# SA_Sch.net
KiCad netlist of a schematic drawn in Altium Designer
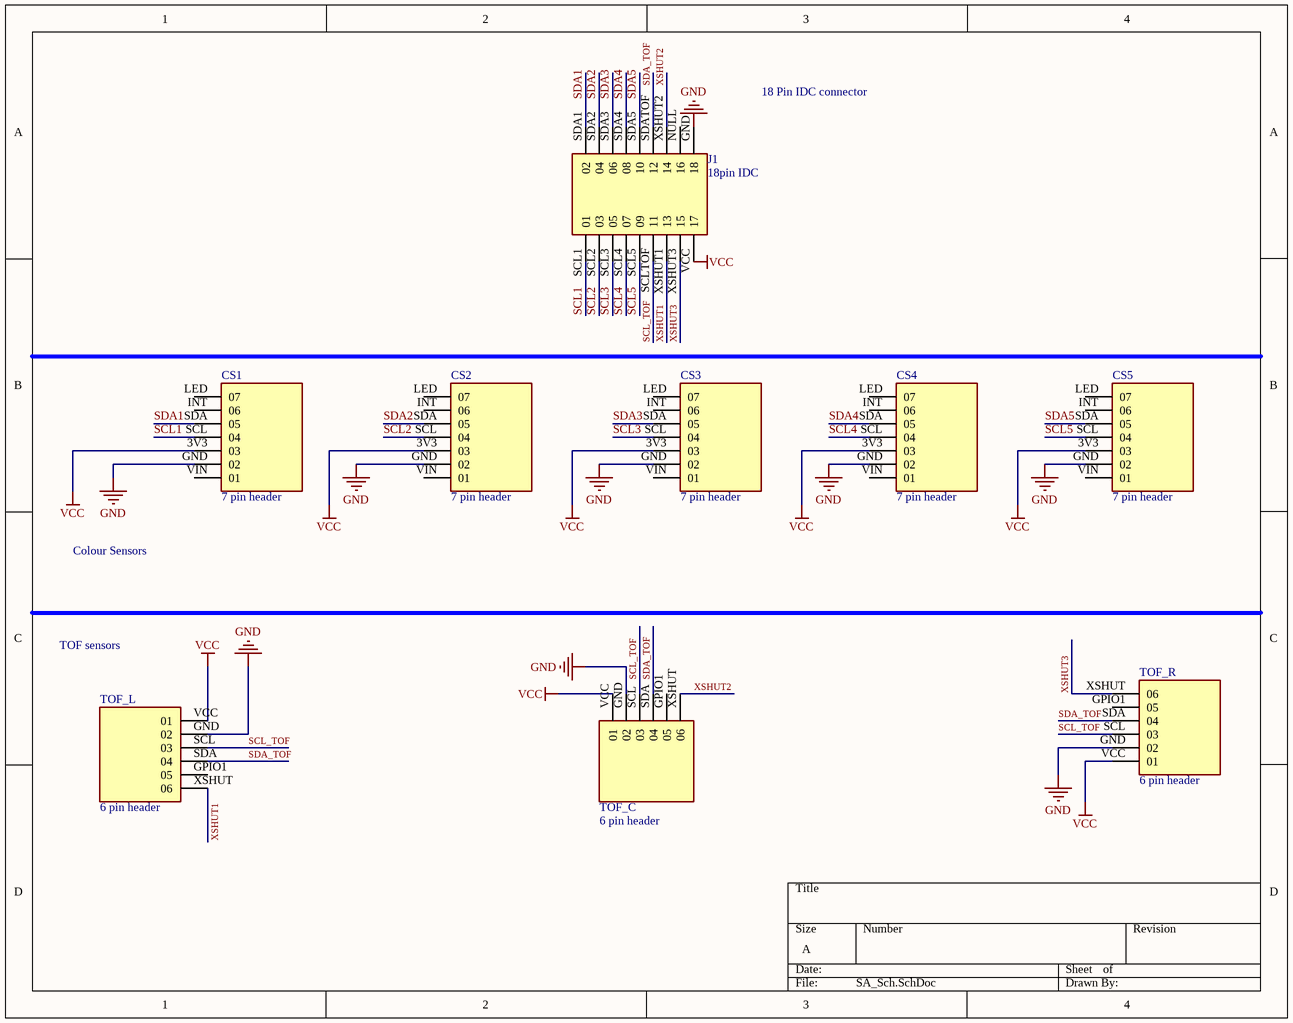
[diagram p0: SA_Sch.SchDoc]

(export (version "E")
  (design (tool "Eeschema 10.0.6"))
  (components
    (comp (ref "CS1")
      (value "7 pin header")
      (footprint "7 pin header holes")
      (description "14 Position Header Connector Male Pin Gold")
      (fields (field (name "MF") "Samtec") (field (name "MP") "TS-114-G-AA"))
      (libsource (lib "SA_SchLib") (part "7 pin header"))
    )
    (comp (ref "CS2")
      (value "7 pin header")
      (footprint "7 pin header holes")
      (description "14 Position Header Connector Male Pin Gold")
      (fields (field (name "MF") "Samtec") (field (name "MP") "TS-114-G-AA"))
      (libsource (lib "SA_SchLib") (part "7 pin header"))
    )
    (comp (ref "CS3")
      (value "7 pin header")
      (footprint "7 pin header holes")
      (description "14 Position Header Connector Male Pin Gold")
      (fields (field (name "MF") "Samtec") (field (name "MP") "TS-114-G-AA"))
      (libsource (lib "SA_SchLib") (part "7 pin header"))
    )
    (comp (ref "CS4")
      (value "7 pin header")
      (footprint "7 pin header holes")
      (description "14 Position Header Connector Male Pin Gold")
      (fields (field (name "MF") "Samtec") (field (name "MP") "TS-114-G-AA"))
      (libsource (lib "SA_SchLib") (part "7 pin header"))
    )
    (comp (ref "CS5")
      (value "7 pin header")
      (footprint "7 pin header holes")
      (description "14 Position Header Connector Male Pin Gold")
      (fields (field (name "MF") "Samtec") (field (name "MP") "TS-114-G-AA"))
      (libsource (lib "SA_SchLib") (part "7 pin header"))
    )
    (comp (ref "J1")
      (value "18pin IDC")
      (footprint "IDC 18 pin")
      (description "Slim Body Double-Row IDC Male Assemblies, 0.100 Pitch")
      (fields (field (name "MF") "SAMTEC") (field (name "MP") "IDMD-10-S-07.00-G"))
      (libsource (lib "SA_SchLib") (part "18pin IDC"))
    )
    (comp (ref "TOF_C")
      (value "6 pin header")
      (footprint "6 pin header")
      (description "6 Position Header Connector Male Pin Gold")
      (fields (field (name "MF") "Samtec") (field (name "MP") "TS-114-G-AA"))
      (libsource (lib "") (part "6 pin header_2"))
    )
    (comp (ref "TOF_L")
      (value "6 pin header")
      (footprint "6 pin header")
      (description "6 Position Header Connector Male Pin Gold")
      (fields (field (name "MF") "Samtec") (field (name "MP") "TS-114-G-AA"))
      (libsource (lib "SA_SchLib") (part "6 pin header"))
    )
    (comp (ref "TOF_R")
      (value "6 pin header")
      (footprint "6 pin header")
      (description "6 Position Header Connector Male Pin Gold")
      (fields (field (name "MF") "Samtec") (field (name "MP") "TS-114-G-AA"))
      (libsource (lib "") (part "6 pin header_1"))
    )
  )
  (nets
    (net (code "1") (name "/SCL1") (class "Default")
      (node (ref "CS1") (pin "SCL") (pinfunction "04_SCL") (pintype "passive"))
      (node (ref "J1") (pin "SCL1") (pinfunction "01_SCL1") (pintype "passive"))
    )
    (net (code "2") (name "/SCL2") (class "Default")
      (node (ref "CS2") (pin "SCL") (pinfunction "04_SCL") (pintype "passive"))
      (node (ref "J1") (pin "SCL2") (pinfunction "03_SCL2") (pintype "passive"))
    )
    (net (code "3") (name "/SCL3") (class "Default")
      (node (ref "CS3") (pin "SCL") (pinfunction "04_SCL") (pintype "passive"))
      (node (ref "J1") (pin "SCL3") (pinfunction "05_SCL3") (pintype "passive"))
    )
    (net (code "4") (name "/SCL4") (class "Default")
      (node (ref "CS4") (pin "SCL") (pinfunction "04_SCL") (pintype "passive"))
      (node (ref "J1") (pin "SCL4") (pinfunction "07_SCL4") (pintype "passive"))
    )
    (net (code "5") (name "/SCL5") (class "Default")
      (node (ref "CS5") (pin "SCL") (pinfunction "04_SCL") (pintype "passive"))
      (node (ref "J1") (pin "SCL5") (pinfunction "09_SCL5") (pintype "passive"))
    )
    (net (code "6") (name "/SCL_TOF") (class "Default")
      (node (ref "J1") (pin "SCLTOF") (pinfunction "11_SCLTOF") (pintype "passive"))
      (node (ref "TOF_C") (pin "SCL") (pinfunction "03_SCL") (pintype "passive"))
      (node (ref "TOF_L") (pin "SCL") (pinfunction "03_SCL") (pintype "passive"))
      (node (ref "TOF_R") (pin "SCL") (pinfunction "03_SCL") (pintype "passive"))
    )
    (net (code "7") (name "/SDA1") (class "Default")
      (node (ref "CS1") (pin "SDA") (pinfunction "05_SDA") (pintype "passive"))
      (node (ref "J1") (pin "SDA1") (pinfunction "02_SDA1") (pintype "passive"))
    )
    (net (code "8") (name "/SDA2") (class "Default")
      (node (ref "CS2") (pin "SDA") (pinfunction "05_SDA") (pintype "passive"))
      (node (ref "J1") (pin "SDA2") (pinfunction "04_SDA2") (pintype "passive"))
    )
    (net (code "9") (name "/SDA3") (class "Default")
      (node (ref "CS3") (pin "SDA") (pinfunction "05_SDA") (pintype "passive"))
      (node (ref "J1") (pin "SDA3") (pinfunction "06_SDA3") (pintype "passive"))
    )
    (net (code "10") (name "/SDA4") (class "Default")
      (node (ref "CS4") (pin "SDA") (pinfunction "05_SDA") (pintype "passive"))
      (node (ref "J1") (pin "SDA4") (pinfunction "08_SDA4") (pintype "passive"))
    )
    (net (code "11") (name "/SDA5") (class "Default")
      (node (ref "CS5") (pin "SDA") (pinfunction "05_SDA") (pintype "passive"))
      (node (ref "J1") (pin "SDA5") (pinfunction "10_SDA5") (pintype "passive"))
    )
    (net (code "12") (name "/SDA_TOF") (class "Default")
      (node (ref "J1") (pin "SDATOF") (pinfunction "12_SDATOF") (pintype "passive"))
      (node (ref "TOF_C") (pin "SDA") (pinfunction "04_SDA") (pintype "passive"))
      (node (ref "TOF_L") (pin "SDA") (pinfunction "04_SDA") (pintype "passive"))
      (node (ref "TOF_R") (pin "SDA") (pinfunction "04_SDA") (pintype "passive"))
    )
    (net (code "13") (name "/XSHUT1") (class "Default")
      (node (ref "J1") (pin "XSHUT1") (pinfunction "13_XSHUT1") (pintype "passive"))
      (node (ref "TOF_L") (pin "XSHUT") (pinfunction "06_XSHUT") (pintype "passive"))
    )
    (net (code "14") (name "/XSHUT2") (class "Default")
      (node (ref "J1") (pin "XSHUT2") (pinfunction "14_XSHUT2") (pintype "passive"))
      (node (ref "TOF_C") (pin "XSHUT") (pinfunction "06_XSHUT") (pintype "passive"))
    )
    (net (code "15") (name "/XSHUT3") (class "Default")
      (node (ref "J1") (pin "XSHUT3") (pinfunction "15_XSHUT3") (pintype "passive"))
      (node (ref "TOF_R") (pin "XSHUT") (pinfunction "06_XSHUT") (pintype "passive"))
    )
    (net (code "16") (name "GND") (class "Default")
      (node (ref "CS1") (pin "GND") (pinfunction "02_GND") (pintype "passive"))
      (node (ref "CS2") (pin "GND") (pinfunction "02_GND") (pintype "passive"))
      (node (ref "CS3") (pin "GND") (pinfunction "02_GND") (pintype "passive"))
      (node (ref "CS4") (pin "GND") (pinfunction "02_GND") (pintype "passive"))
      (node (ref "CS5") (pin "GND") (pinfunction "02_GND") (pintype "passive"))
      (node (ref "J1") (pin "GND") (pinfunction "18_GND") (pintype "passive"))
      (node (ref "TOF_C") (pin "GND") (pinfunction "02_GND") (pintype "passive"))
      (node (ref "TOF_L") (pin "GND") (pinfunction "02_GND") (pintype "passive"))
      (node (ref "TOF_R") (pin "GND") (pinfunction "02_GND") (pintype "passive"))
    )
    (net (code "17") (name "VCC") (class "Default")
      (node (ref "CS1") (pin "3V3") (pinfunction "03_3V3") (pintype "passive"))
      (node (ref "CS2") (pin "3V3") (pinfunction "03_3V3") (pintype "passive"))
      (node (ref "CS3") (pin "3V3") (pinfunction "03_3V3") (pintype "passive"))
      (node (ref "CS4") (pin "3V3") (pinfunction "03_3V3") (pintype "passive"))
      (node (ref "CS5") (pin "3V3") (pinfunction "03_3V3") (pintype "passive"))
      (node (ref "J1") (pin "VCC") (pinfunction "17_VCC") (pintype "passive"))
      (node (ref "TOF_C") (pin "VCC") (pinfunction "01_VCC") (pintype "passive"))
      (node (ref "TOF_L") (pin "VCC") (pinfunction "01_VCC") (pintype "passive"))
      (node (ref "TOF_R") (pin "VCC") (pinfunction "01_VCC") (pintype "passive"))
    )
    (net (code "18") (name "unconnected-(CS1-01-PadVIN)") (class "Default")
      (node (ref "CS1") (pin "VIN") (pinfunction "01_VIN") (pintype "passive"))
    )
    (net (code "19") (name "unconnected-(CS1-06-PadINT)") (class "Default")
      (node (ref "CS1") (pin "INT") (pinfunction "06_INT") (pintype "passive"))
    )
    (net (code "20") (name "unconnected-(CS1-07-PadLED)") (class "Default")
      (node (ref "CS1") (pin "LED") (pinfunction "07_LED") (pintype "passive"))
    )
    (net (code "21") (name "unconnected-(CS2-01-PadVIN)") (class "Default")
      (node (ref "CS2") (pin "VIN") (pinfunction "01_VIN") (pintype "passive"))
    )
    (net (code "22") (name "unconnected-(CS2-06-PadINT)") (class "Default")
      (node (ref "CS2") (pin "INT") (pinfunction "06_INT") (pintype "passive"))
    )
    (net (code "23") (name "unconnected-(CS2-07-PadLED)") (class "Default")
      (node (ref "CS2") (pin "LED") (pinfunction "07_LED") (pintype "passive"))
    )
    (net (code "24") (name "unconnected-(CS3-01-PadVIN)") (class "Default")
      (node (ref "CS3") (pin "VIN") (pinfunction "01_VIN") (pintype "passive"))
    )
    (net (code "25") (name "unconnected-(CS3-06-PadINT)") (class "Default")
      (node (ref "CS3") (pin "INT") (pinfunction "06_INT") (pintype "passive"))
    )
    (net (code "26") (name "unconnected-(CS3-07-PadLED)") (class "Default")
      (node (ref "CS3") (pin "LED") (pinfunction "07_LED") (pintype "passive"))
    )
    (net (code "27") (name "unconnected-(CS4-01-PadVIN)") (class "Default")
      (node (ref "CS4") (pin "VIN") (pinfunction "01_VIN") (pintype "passive"))
    )
    (net (code "28") (name "unconnected-(CS4-06-PadINT)") (class "Default")
      (node (ref "CS4") (pin "INT") (pinfunction "06_INT") (pintype "passive"))
    )
    (net (code "29") (name "unconnected-(CS4-07-PadLED)") (class "Default")
      (node (ref "CS4") (pin "LED") (pinfunction "07_LED") (pintype "passive"))
    )
    (net (code "30") (name "unconnected-(CS5-01-PadVIN)") (class "Default")
      (node (ref "CS5") (pin "VIN") (pinfunction "01_VIN") (pintype "passive"))
    )
    (net (code "31") (name "unconnected-(CS5-06-PadINT)") (class "Default")
      (node (ref "CS5") (pin "INT") (pinfunction "06_INT") (pintype "passive"))
    )
    (net (code "32") (name "unconnected-(CS5-07-PadLED)") (class "Default")
      (node (ref "CS5") (pin "LED") (pinfunction "07_LED") (pintype "passive"))
    )
    (net (code "33") (name "unconnected-(J1-16-PadNULL)") (class "Default")
      (node (ref "J1") (pin "NULL") (pinfunction "16_NULL") (pintype "passive"))
    )
    (net (code "34") (name "unconnected-(TOF_C-05-PadGPIO1)") (class "Default")
      (node (ref "TOF_C") (pin "GPIO1") (pinfunction "05_GPIO1") (pintype "passive"))
    )
    (net (code "35") (name "unconnected-(TOF_L-05-PadGPIO1)") (class "Default")
      (node (ref "TOF_L") (pin "GPIO1") (pinfunction "05_GPIO1") (pintype "passive"))
    )
    (net (code "36") (name "unconnected-(TOF_R-05-PadGPIO1)") (class "Default")
      (node (ref "TOF_R") (pin "GPIO1") (pinfunction "05_GPIO1") (pintype "passive"))
    )
  )
)
